# LED0_7.net
KiCad netlist of a schematic drawn in Altium Designer
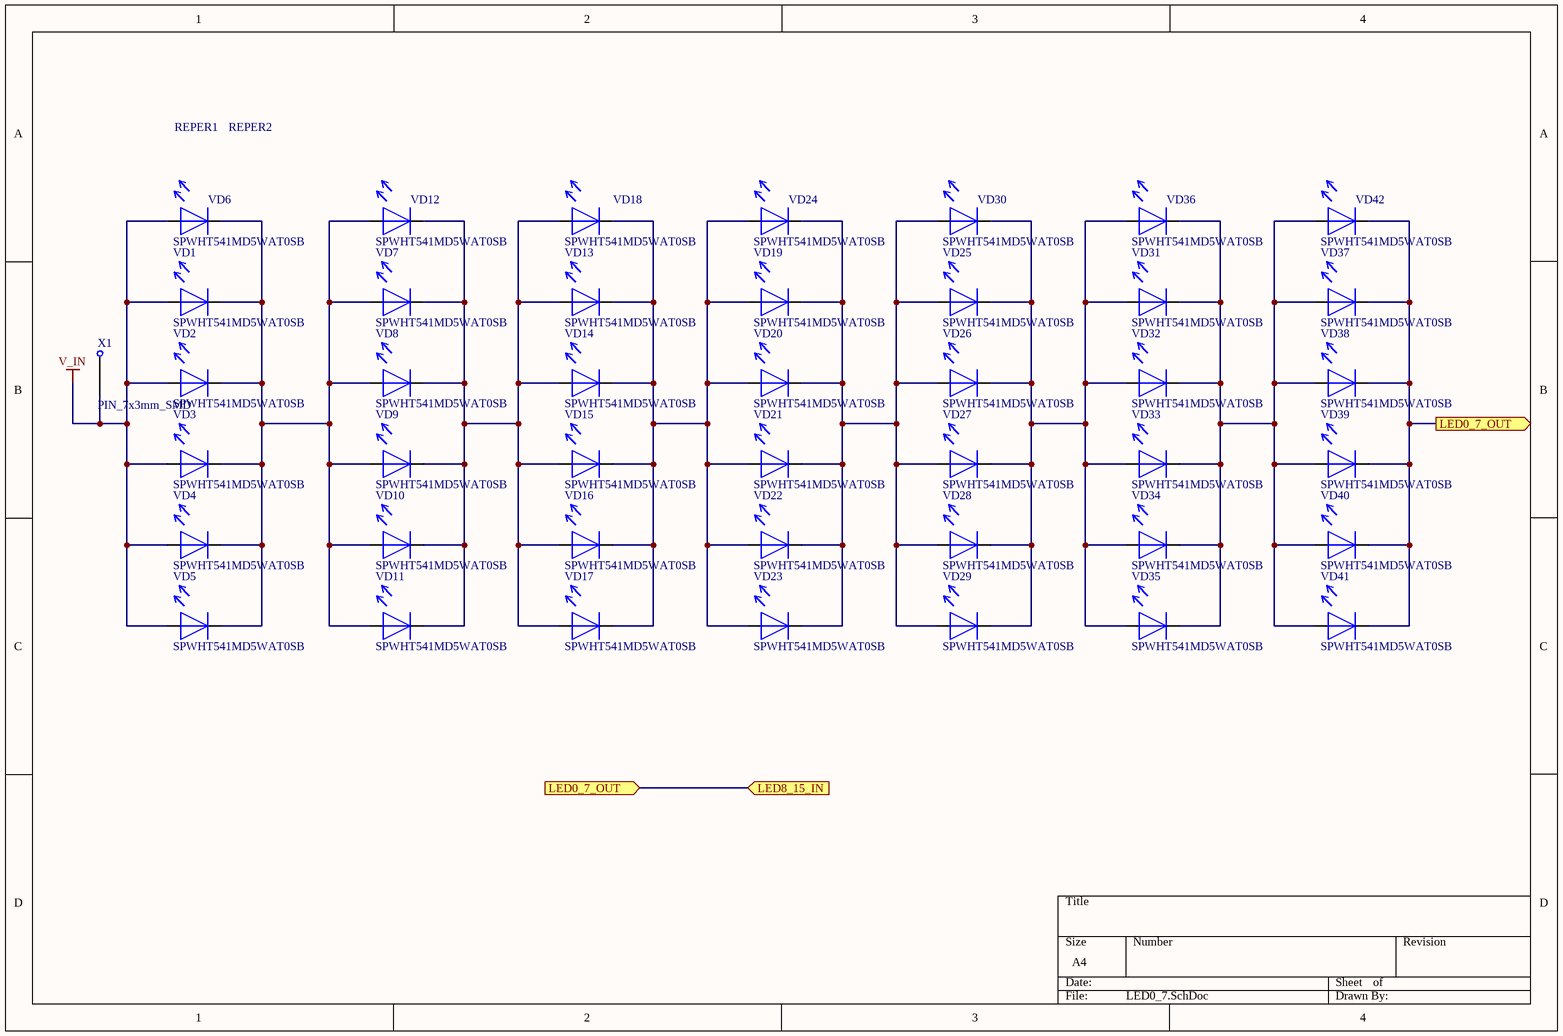
[diagram p0: LED0_7.SchDoc]

(export (version "E")
  (design (tool "Eeschema 10.0.6"))
  (components
    (comp (ref "REPER1")
      (value "REPER1.2")
      (footprint "REPER1.2")
      (libsource (lib "gprs_modem") (part "REPER1.2"))
    )
    (comp (ref "REPER2")
      (value "REPER1.2")
      (footprint "REPER1.2")
      (libsource (lib "gprs_modem") (part "REPER1.2"))
    )
    (comp (ref "VD1")
      (value "SPWHT541MD5WAT0SB")
      (footprint "LED_SAMSUNG")
      (libsource (lib "gprs_modem") (part "LED SPWHT541MD5WAT0SB"))
    )
    (comp (ref "VD2")
      (value "SPWHT541MD5WAT0SB")
      (footprint "LED_SAMSUNG")
      (libsource (lib "gprs_modem") (part "LED SPWHT541MD5WAT0SB"))
    )
    (comp (ref "VD3")
      (value "SPWHT541MD5WAT0SB")
      (footprint "LED_SAMSUNG")
      (libsource (lib "gprs_modem") (part "LED SPWHT541MD5WAT0SB"))
    )
    (comp (ref "VD4")
      (value "SPWHT541MD5WAT0SB")
      (footprint "LED_SAMSUNG")
      (libsource (lib "gprs_modem") (part "LED SPWHT541MD5WAT0SB"))
    )
    (comp (ref "VD5")
      (value "SPWHT541MD5WAT0SB")
      (footprint "LED_SAMSUNG")
      (libsource (lib "gprs_modem") (part "LED SPWHT541MD5WAT0SB"))
    )
    (comp (ref "VD6")
      (value "SPWHT541MD5WAT0SB")
      (footprint "LED_SAMSUNG")
      (libsource (lib "gprs_modem") (part "LED SPWHT541MD5WAT0SB"))
    )
    (comp (ref "VD7")
      (value "SPWHT541MD5WAT0SB")
      (footprint "LED_SAMSUNG")
      (libsource (lib "gprs_modem") (part "LED SPWHT541MD5WAT0SB"))
    )
    (comp (ref "VD8")
      (value "SPWHT541MD5WAT0SB")
      (footprint "LED_SAMSUNG")
      (libsource (lib "gprs_modem") (part "LED SPWHT541MD5WAT0SB"))
    )
    (comp (ref "VD9")
      (value "SPWHT541MD5WAT0SB")
      (footprint "LED_SAMSUNG")
      (libsource (lib "gprs_modem") (part "LED SPWHT541MD5WAT0SB"))
    )
    (comp (ref "VD10")
      (value "SPWHT541MD5WAT0SB")
      (footprint "LED_SAMSUNG")
      (libsource (lib "gprs_modem") (part "LED SPWHT541MD5WAT0SB"))
    )
    (comp (ref "VD11")
      (value "SPWHT541MD5WAT0SB")
      (footprint "LED_SAMSUNG")
      (libsource (lib "gprs_modem") (part "LED SPWHT541MD5WAT0SB"))
    )
    (comp (ref "VD12")
      (value "SPWHT541MD5WAT0SB")
      (footprint "LED_SAMSUNG")
      (libsource (lib "gprs_modem") (part "LED SPWHT541MD5WAT0SB"))
    )
    (comp (ref "VD13")
      (value "SPWHT541MD5WAT0SB")
      (footprint "LED_SAMSUNG")
      (libsource (lib "gprs_modem") (part "LED SPWHT541MD5WAT0SB"))
    )
    (comp (ref "VD14")
      (value "SPWHT541MD5WAT0SB")
      (footprint "LED_SAMSUNG")
      (libsource (lib "gprs_modem") (part "LED SPWHT541MD5WAT0SB"))
    )
    (comp (ref "VD15")
      (value "SPWHT541MD5WAT0SB")
      (footprint "LED_SAMSUNG")
      (libsource (lib "gprs_modem") (part "LED SPWHT541MD5WAT0SB"))
    )
    (comp (ref "VD16")
      (value "SPWHT541MD5WAT0SB")
      (footprint "LED_SAMSUNG")
      (libsource (lib "gprs_modem") (part "LED SPWHT541MD5WAT0SB"))
    )
    (comp (ref "VD17")
      (value "SPWHT541MD5WAT0SB")
      (footprint "LED_SAMSUNG")
      (libsource (lib "gprs_modem") (part "LED SPWHT541MD5WAT0SB"))
    )
    (comp (ref "VD18")
      (value "SPWHT541MD5WAT0SB")
      (footprint "LED_SAMSUNG")
      (libsource (lib "gprs_modem") (part "LED SPWHT541MD5WAT0SB"))
    )
    (comp (ref "VD19")
      (value "SPWHT541MD5WAT0SB")
      (footprint "LED_SAMSUNG")
      (libsource (lib "gprs_modem") (part "LED SPWHT541MD5WAT0SB"))
    )
    (comp (ref "VD20")
      (value "SPWHT541MD5WAT0SB")
      (footprint "LED_SAMSUNG")
      (libsource (lib "gprs_modem") (part "LED SPWHT541MD5WAT0SB"))
    )
    (comp (ref "VD21")
      (value "SPWHT541MD5WAT0SB")
      (footprint "LED_SAMSUNG")
      (libsource (lib "gprs_modem") (part "LED SPWHT541MD5WAT0SB"))
    )
    (comp (ref "VD22")
      (value "SPWHT541MD5WAT0SB")
      (footprint "LED_SAMSUNG")
      (libsource (lib "gprs_modem") (part "LED SPWHT541MD5WAT0SB"))
    )
    (comp (ref "VD23")
      (value "SPWHT541MD5WAT0SB")
      (footprint "LED_SAMSUNG")
      (libsource (lib "gprs_modem") (part "LED SPWHT541MD5WAT0SB"))
    )
    (comp (ref "VD24")
      (value "SPWHT541MD5WAT0SB")
      (footprint "LED_SAMSUNG")
      (libsource (lib "gprs_modem") (part "LED SPWHT541MD5WAT0SB"))
    )
    (comp (ref "VD25")
      (value "SPWHT541MD5WAT0SB")
      (footprint "LED_SAMSUNG")
      (libsource (lib "gprs_modem") (part "LED SPWHT541MD5WAT0SB"))
    )
    (comp (ref "VD26")
      (value "SPWHT541MD5WAT0SB")
      (footprint "LED_SAMSUNG")
      (libsource (lib "gprs_modem") (part "LED SPWHT541MD5WAT0SB"))
    )
    (comp (ref "VD27")
      (value "SPWHT541MD5WAT0SB")
      (footprint "LED_SAMSUNG")
      (libsource (lib "gprs_modem") (part "LED SPWHT541MD5WAT0SB"))
    )
    (comp (ref "VD28")
      (value "SPWHT541MD5WAT0SB")
      (footprint "LED_SAMSUNG")
      (libsource (lib "gprs_modem") (part "LED SPWHT541MD5WAT0SB"))
    )
    (comp (ref "VD29")
      (value "SPWHT541MD5WAT0SB")
      (footprint "LED_SAMSUNG")
      (libsource (lib "gprs_modem") (part "LED SPWHT541MD5WAT0SB"))
    )
    (comp (ref "VD30")
      (value "SPWHT541MD5WAT0SB")
      (footprint "LED_SAMSUNG")
      (libsource (lib "gprs_modem") (part "LED SPWHT541MD5WAT0SB"))
    )
    (comp (ref "VD31")
      (value "SPWHT541MD5WAT0SB")
      (footprint "LED_SAMSUNG")
      (libsource (lib "gprs_modem") (part "LED SPWHT541MD5WAT0SB"))
    )
    (comp (ref "VD32")
      (value "SPWHT541MD5WAT0SB")
      (footprint "LED_SAMSUNG")
      (libsource (lib "gprs_modem") (part "LED SPWHT541MD5WAT0SB"))
    )
    (comp (ref "VD33")
      (value "SPWHT541MD5WAT0SB")
      (footprint "LED_SAMSUNG")
      (libsource (lib "gprs_modem") (part "LED SPWHT541MD5WAT0SB"))
    )
    (comp (ref "VD34")
      (value "SPWHT541MD5WAT0SB")
      (footprint "LED_SAMSUNG")
      (libsource (lib "gprs_modem") (part "LED SPWHT541MD5WAT0SB"))
    )
    (comp (ref "VD35")
      (value "SPWHT541MD5WAT0SB")
      (footprint "LED_SAMSUNG")
      (libsource (lib "gprs_modem") (part "LED SPWHT541MD5WAT0SB"))
    )
    (comp (ref "VD36")
      (value "SPWHT541MD5WAT0SB")
      (footprint "LED_SAMSUNG")
      (libsource (lib "gprs_modem") (part "LED SPWHT541MD5WAT0SB"))
    )
    (comp (ref "VD37")
      (value "SPWHT541MD5WAT0SB")
      (footprint "LED_SAMSUNG")
      (libsource (lib "gprs_modem") (part "LED SPWHT541MD5WAT0SB"))
    )
    (comp (ref "VD38")
      (value "SPWHT541MD5WAT0SB")
      (footprint "LED_SAMSUNG")
      (libsource (lib "gprs_modem") (part "LED SPWHT541MD5WAT0SB"))
    )
    (comp (ref "VD39")
      (value "SPWHT541MD5WAT0SB")
      (footprint "LED_SAMSUNG")
      (libsource (lib "gprs_modem") (part "LED SPWHT541MD5WAT0SB"))
    )
    (comp (ref "VD40")
      (value "SPWHT541MD5WAT0SB")
      (footprint "LED_SAMSUNG")
      (libsource (lib "gprs_modem") (part "LED SPWHT541MD5WAT0SB"))
    )
    (comp (ref "VD41")
      (value "SPWHT541MD5WAT0SB")
      (footprint "LED_SAMSUNG")
      (libsource (lib "gprs_modem") (part "LED SPWHT541MD5WAT0SB"))
    )
    (comp (ref "VD42")
      (value "SPWHT541MD5WAT0SB")
      (footprint "LED_SAMSUNG")
      (libsource (lib "gprs_modem") (part "LED SPWHT541MD5WAT0SB"))
    )
    (comp (ref "X1")
      (value "PIN_7x3mm_SMD")
      (footprint "PIN_7x3mm_SMD")
      (libsource (lib "gprs_modem") (part "PIN_7x3mm_SMD"))
    )
  )
  (nets
    (net (code "1") (name "/LED0_7_OUT") (class "Default")
      (node (ref "VD37") (pin "2") (pintype "passive"))
      (node (ref "VD38") (pin "2") (pintype "passive"))
      (node (ref "VD39") (pin "2") (pintype "passive"))
      (node (ref "VD40") (pin "2") (pintype "passive"))
      (node (ref "VD41") (pin "2") (pintype "passive"))
      (node (ref "VD42") (pin "2") (pintype "passive"))
    )
    (net (code "2") (name "Net-(VD1-Pad2)") (class "Default")
      (node (ref "VD1") (pin "2") (pintype "passive"))
      (node (ref "VD10") (pin "1") (pintype "passive"))
      (node (ref "VD11") (pin "1") (pintype "passive"))
      (node (ref "VD12") (pin "1") (pintype "passive"))
      (node (ref "VD2") (pin "2") (pintype "passive"))
      (node (ref "VD3") (pin "2") (pintype "passive"))
      (node (ref "VD4") (pin "2") (pintype "passive"))
      (node (ref "VD5") (pin "2") (pintype "passive"))
      (node (ref "VD6") (pin "2") (pintype "passive"))
      (node (ref "VD7") (pin "1") (pintype "passive"))
      (node (ref "VD8") (pin "1") (pintype "passive"))
      (node (ref "VD9") (pin "1") (pintype "passive"))
    )
    (net (code "3") (name "Net-(VD10-Pad2)") (class "Default")
      (node (ref "VD10") (pin "2") (pintype "passive"))
      (node (ref "VD11") (pin "2") (pintype "passive"))
      (node (ref "VD12") (pin "2") (pintype "passive"))
      (node (ref "VD13") (pin "1") (pintype "passive"))
      (node (ref "VD14") (pin "1") (pintype "passive"))
      (node (ref "VD15") (pin "1") (pintype "passive"))
      (node (ref "VD16") (pin "1") (pintype "passive"))
      (node (ref "VD17") (pin "1") (pintype "passive"))
      (node (ref "VD18") (pin "1") (pintype "passive"))
      (node (ref "VD7") (pin "2") (pintype "passive"))
      (node (ref "VD8") (pin "2") (pintype "passive"))
      (node (ref "VD9") (pin "2") (pintype "passive"))
    )
    (net (code "4") (name "Net-(VD13-Pad2)") (class "Default")
      (node (ref "VD13") (pin "2") (pintype "passive"))
      (node (ref "VD14") (pin "2") (pintype "passive"))
      (node (ref "VD15") (pin "2") (pintype "passive"))
      (node (ref "VD16") (pin "2") (pintype "passive"))
      (node (ref "VD17") (pin "2") (pintype "passive"))
      (node (ref "VD18") (pin "2") (pintype "passive"))
      (node (ref "VD19") (pin "1") (pintype "passive"))
      (node (ref "VD20") (pin "1") (pintype "passive"))
      (node (ref "VD21") (pin "1") (pintype "passive"))
      (node (ref "VD22") (pin "1") (pintype "passive"))
      (node (ref "VD23") (pin "1") (pintype "passive"))
      (node (ref "VD24") (pin "1") (pintype "passive"))
    )
    (net (code "5") (name "Net-(VD19-Pad2)") (class "Default")
      (node (ref "VD19") (pin "2") (pintype "passive"))
      (node (ref "VD20") (pin "2") (pintype "passive"))
      (node (ref "VD21") (pin "2") (pintype "passive"))
      (node (ref "VD22") (pin "2") (pintype "passive"))
      (node (ref "VD23") (pin "2") (pintype "passive"))
      (node (ref "VD24") (pin "2") (pintype "passive"))
      (node (ref "VD25") (pin "1") (pintype "passive"))
      (node (ref "VD26") (pin "1") (pintype "passive"))
      (node (ref "VD27") (pin "1") (pintype "passive"))
      (node (ref "VD28") (pin "1") (pintype "passive"))
      (node (ref "VD29") (pin "1") (pintype "passive"))
      (node (ref "VD30") (pin "1") (pintype "passive"))
    )
    (net (code "6") (name "Net-(VD25-Pad2)") (class "Default")
      (node (ref "VD25") (pin "2") (pintype "passive"))
      (node (ref "VD26") (pin "2") (pintype "passive"))
      (node (ref "VD27") (pin "2") (pintype "passive"))
      (node (ref "VD28") (pin "2") (pintype "passive"))
      (node (ref "VD29") (pin "2") (pintype "passive"))
      (node (ref "VD30") (pin "2") (pintype "passive"))
      (node (ref "VD31") (pin "1") (pintype "passive"))
      (node (ref "VD32") (pin "1") (pintype "passive"))
      (node (ref "VD33") (pin "1") (pintype "passive"))
      (node (ref "VD34") (pin "1") (pintype "passive"))
      (node (ref "VD35") (pin "1") (pintype "passive"))
      (node (ref "VD36") (pin "1") (pintype "passive"))
    )
    (net (code "7") (name "Net-(VD31-Pad2)") (class "Default")
      (node (ref "VD31") (pin "2") (pintype "passive"))
      (node (ref "VD32") (pin "2") (pintype "passive"))
      (node (ref "VD33") (pin "2") (pintype "passive"))
      (node (ref "VD34") (pin "2") (pintype "passive"))
      (node (ref "VD35") (pin "2") (pintype "passive"))
      (node (ref "VD36") (pin "2") (pintype "passive"))
      (node (ref "VD37") (pin "1") (pintype "passive"))
      (node (ref "VD38") (pin "1") (pintype "passive"))
      (node (ref "VD39") (pin "1") (pintype "passive"))
      (node (ref "VD40") (pin "1") (pintype "passive"))
      (node (ref "VD41") (pin "1") (pintype "passive"))
      (node (ref "VD42") (pin "1") (pintype "passive"))
    )
    (net (code "8") (name "V_IN") (class "Default")
      (node (ref "VD1") (pin "1") (pintype "passive"))
      (node (ref "VD2") (pin "1") (pintype "passive"))
      (node (ref "VD3") (pin "1") (pintype "passive"))
      (node (ref "VD4") (pin "1") (pintype "passive"))
      (node (ref "VD5") (pin "1") (pintype "passive"))
      (node (ref "VD6") (pin "1") (pintype "passive"))
      (node (ref "X1") (pin "1") (pinfunction "1_1") (pintype "passive"))
    )
    (net (code "9") (name "unconnected-(REPER1-Pad1)") (class "Default")
      (node (ref "REPER1") (pin "1") (pintype "passive"))
    )
    (net (code "10") (name "unconnected-(REPER2-Pad1)") (class "Default")
      (node (ref "REPER2") (pin "1") (pintype "passive"))
    )
  )
)
